# esp32.net
KiCad netlist of a schematic drawn in Altium Designer
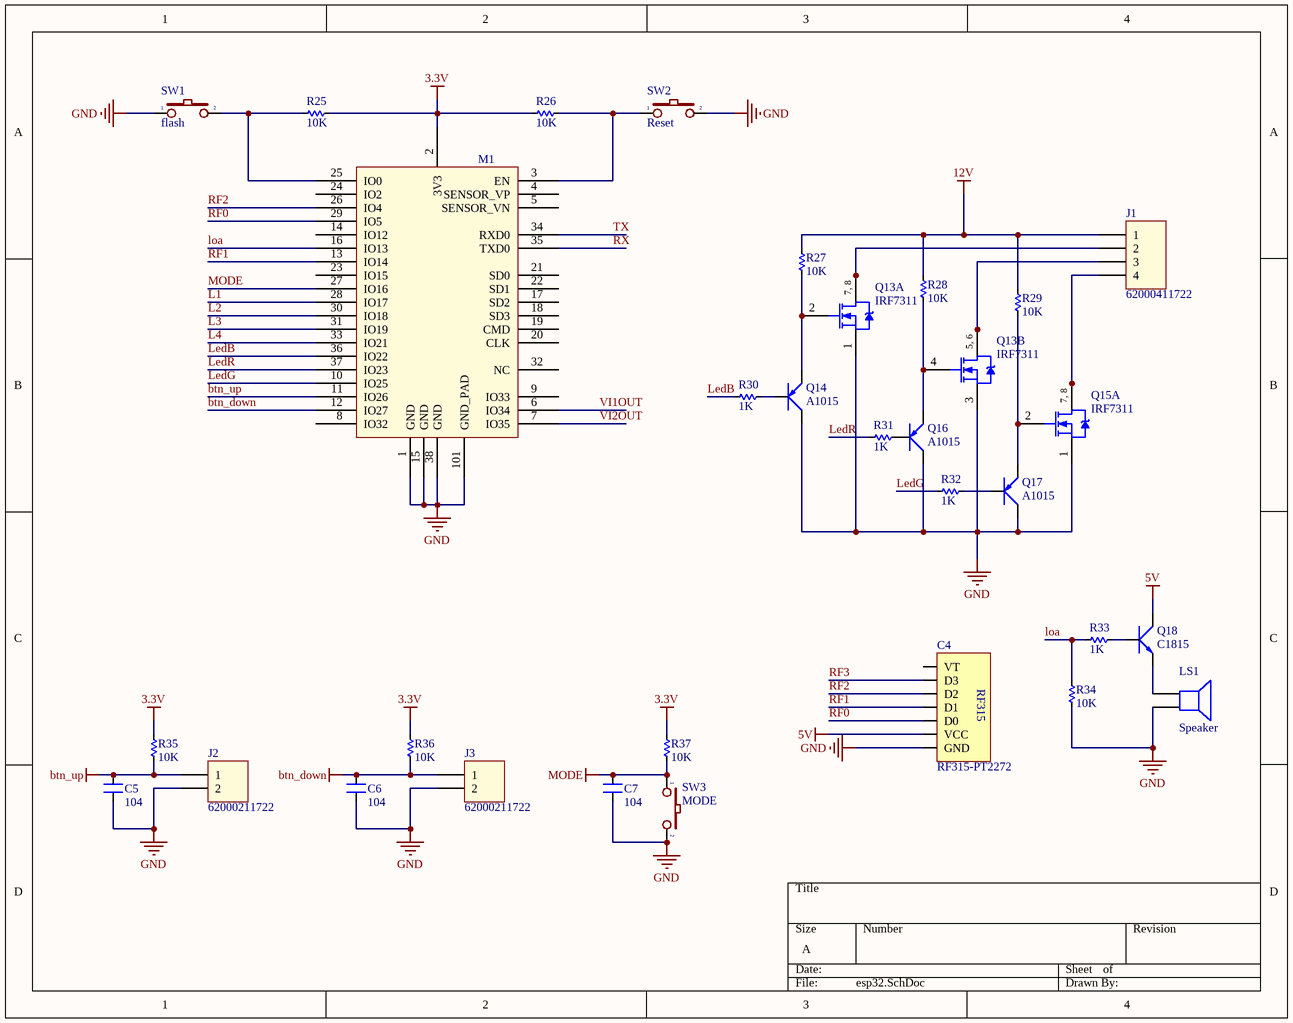
[diagram p0: esp32.SchDoc]

(export (version "E")
  (design (tool "Eeschema 10.0.6"))
  (components
    (comp (ref "C4")
      (value "RF315-PT2272")
      (footprint "RF315-2272")
      (fields
        (field (name "MANUFACTURER") "Würth Elektronik eiSos GmbH")
        (field (name "PARTNO") "613004143121")
        (field (name "CREATED BY") "Karrer Zheng")
      )
      (libsource (lib "LIBRARY") (part "RF315-PT2272"))
    )
    (comp (ref "C5")
      (value "104")
      (footprint "SM-CAP-0805")
      (fields (field (name "DESIGNED BY") "VanDungEvn"))
      (libsource (lib "electronicvn-library1") (part "CN"))
    )
    (comp (ref "C6")
      (value "104")
      (footprint "SM-CAP-0805")
      (fields (field (name "DESIGNED BY") "VanDungEvn"))
      (libsource (lib "electronicvn-library1") (part "CN"))
    )
    (comp (ref "C7")
      (value "104")
      (footprint "SM-CAP-0805")
      (fields (field (name "DESIGNED BY") "VanDungEvn"))
      (libsource (lib "electronicvn-library1") (part "CN"))
    )
    (comp (ref "J1")
      (value "62000411722")
      (footprint "62000411722")
      (description "WR-WTB 2.00mm Male Horizontal Shrouded Header, 4p")
      (fields (field (name "PUBLISHER") "Wurth Elektronik"))
      (libsource (lib "Header2.0") (part "62000411722"))
    )
    (comp (ref "J2")
      (value "62000211722")
      (footprint "62000211722")
      (description "WR-WTB 2.00mm Male Horizontal Shrouded Header, 2p")
      (fields (field (name "PUBLISHER") "Wurth Elektronik"))
      (libsource (lib "Header2.0") (part "62000211722"))
    )
    (comp (ref "J3")
      (value "62000211722")
      (footprint "62000211722")
      (description "WR-WTB 2.00mm Male Horizontal Shrouded Header, 2p")
      (fields (field (name "PUBLISHER") "Wurth Elektronik"))
      (libsource (lib "Header2.0") (part "62000211722"))
    )
    (comp (ref "LS1")
      (value "Speaker")
      (footprint "SPEAKER")
      (description "Loudspeaker")
      (fields (field (name "PUBLISHER") "Altium Limited"))
      (libsource (lib "LIBTanCN") (part "Speaker"))
    )
    (comp (ref "M1")
      (value "ESP32S_Module")
      (footprint "ESP32S")
      (description "Esp-32S")
      (libsource (lib "ESP32S") (part "ESP32S_Module"))
    )
    (comp (ref "Q13")
      (value "IRF7311")
      (footprint "SO-8_N")
      (description "HEXFET Power MOSFET")
      (fields (field (name "PUBLISHER") "Altium Limited"))
      (libsource (lib "IR Discrete MOSFET - Power") (part "IRF7101"))
    )
    (comp (ref "Q14")
      (value "A1015")
      (footprint "SOT23B")
      (description "PNP 600mW, ECB")
      (libsource (lib "electronicvn-library1") (part "A1015"))
    )
    (comp (ref "Q15")
      (value "IRF7311")
      (footprint "SO-8_N")
      (description "HEXFET Power MOSFET")
      (fields (field (name "PUBLISHER") "Altium Limited"))
      (libsource (lib "IR Discrete MOSFET - Power") (part "IRF7101"))
    )
    (comp (ref "Q16")
      (value "A1015")
      (footprint "SOT23B")
      (description "PNP 600mW, ECB")
      (libsource (lib "electronicvn-library1") (part "A1015"))
    )
    (comp (ref "Q17")
      (value "A1015")
      (footprint "SOT23B")
      (description "PNP 600mW, ECB")
      (libsource (lib "electronicvn-library1") (part "A1015"))
    )
    (comp (ref "Q18")
      (value "C1815")
      (footprint "SOT23B")
      (description "NPN 600mW, ECB")
      (libsource (lib "electronicvn-library1") (part "C1815"))
    )
    (comp (ref "R25")
      (value "10K")
      (footprint "RES-SMD-0805")
      (description "Resistor")
      (fields
        (field (name "MANUFACTURER") "Generic Components")
        (field (name "PUBLISHER") "Altium Hobart Technology Centre")
      )
      (libsource (lib "LIBRARY") (part "Res-SMD"))
    )
    (comp (ref "R26")
      (value "10K")
      (footprint "RES-SMD-0805")
      (description "Resistor")
      (fields
        (field (name "MANUFACTURER") "Generic Components")
        (field (name "PUBLISHER") "Altium Hobart Technology Centre")
      )
      (libsource (lib "LIBRARY") (part "Res-SMD"))
    )
    (comp (ref "R27")
      (value "10K")
      (footprint "RES-SMD-0805")
      (description "Resistor")
      (fields
        (field (name "MANUFACTURER") "Generic Components")
        (field (name "PUBLISHER") "Altium Hobart Technology Centre")
      )
      (libsource (lib "LIBRARY") (part "Res-SMD"))
    )
    (comp (ref "R28")
      (value "10K")
      (footprint "RES-SMD-0805")
      (description "Resistor")
      (fields
        (field (name "MANUFACTURER") "Generic Components")
        (field (name "PUBLISHER") "Altium Hobart Technology Centre")
      )
      (libsource (lib "LIBRARY") (part "Res-SMD"))
    )
    (comp (ref "R29")
      (value "10K")
      (footprint "RES-SMD-0805")
      (description "Resistor")
      (fields
        (field (name "MANUFACTURER") "Generic Components")
        (field (name "PUBLISHER") "Altium Hobart Technology Centre")
      )
      (libsource (lib "LIBRARY") (part "Res-SMD"))
    )
    (comp (ref "R30")
      (value "1K")
      (footprint "RES-SMD-0805")
      (description "Resistor")
      (fields
        (field (name "MANUFACTURER") "Generic Components")
        (field (name "PUBLISHER") "Altium Hobart Technology Centre")
      )
      (libsource (lib "LIBRARY") (part "Res-SMD"))
    )
    (comp (ref "R31")
      (value "1K")
      (footprint "RES-SMD-0805")
      (description "Resistor")
      (fields
        (field (name "MANUFACTURER") "Generic Components")
        (field (name "PUBLISHER") "Altium Hobart Technology Centre")
      )
      (libsource (lib "LIBRARY") (part "Res-SMD"))
    )
    (comp (ref "R32")
      (value "1K")
      (footprint "RES-SMD-0805")
      (description "Resistor")
      (fields
        (field (name "MANUFACTURER") "Generic Components")
        (field (name "PUBLISHER") "Altium Hobart Technology Centre")
      )
      (libsource (lib "LIBRARY") (part "Res-SMD"))
    )
    (comp (ref "R33")
      (value "1K")
      (footprint "RES-SMD-0805")
      (description "Resistor")
      (fields
        (field (name "MANUFACTURER") "Generic Components")
        (field (name "PUBLISHER") "Altium Hobart Technology Centre")
      )
      (libsource (lib "LIBRARY") (part "Res-SMD"))
    )
    (comp (ref "R34")
      (value "10K")
      (footprint "RES-SMD-0805")
      (description "Resistor")
      (fields
        (field (name "MANUFACTURER") "Generic Components")
        (field (name "PUBLISHER") "Altium Hobart Technology Centre")
      )
      (libsource (lib "LIBRARY") (part "Res-SMD"))
    )
    (comp (ref "R35")
      (value "10K")
      (footprint "RES-SMD-0805")
      (description "Resistor")
      (fields
        (field (name "MANUFACTURER") "Generic Components")
        (field (name "PUBLISHER") "Altium Hobart Technology Centre")
      )
      (libsource (lib "LIBRARY") (part "Res-SMD"))
    )
    (comp (ref "R36")
      (value "10K")
      (footprint "RES-SMD-0805")
      (description "Resistor")
      (fields
        (field (name "MANUFACTURER") "Generic Components")
        (field (name "PUBLISHER") "Altium Hobart Technology Centre")
      )
      (libsource (lib "LIBRARY") (part "Res-SMD"))
    )
    (comp (ref "R37")
      (value "10K")
      (footprint "RES-SMD-0805")
      (description "Resistor")
      (fields
        (field (name "MANUFACTURER") "Generic Components")
        (field (name "PUBLISHER") "Altium Hobart Technology Centre")
      )
      (libsource (lib "LIBRARY") (part "Res-SMD"))
    )
    (comp (ref "SW1")
      (value "flash")
      (footprint "SW-DIP1-1")
      (description "Switch button 2 pin")
      (libsource (lib "LIBRARY") (part "SW2"))
    )
    (comp (ref "SW2")
      (value "Reset")
      (footprint "SW1-SMD")
      (description "Switch button 2 pin")
      (libsource (lib "LIBRARY") (part "SW2"))
    )
    (comp (ref "SW3")
      (value "MODE")
      (footprint "SW-DIP1-1")
      (description "Switch button 2 pin")
      (libsource (lib "LIBRARY") (part "SW2"))
    )
  )
  (nets
    (net (code "1") (name "/L1") (class "Default")
      (node (ref "M1") (pin "28") (pinfunction "IO17_28") (pintype "passive"))
    )
    (net (code "2") (name "/L2") (class "Default")
      (node (ref "M1") (pin "30") (pinfunction "IO18_30") (pintype "passive"))
    )
    (net (code "3") (name "/L3") (class "Default")
      (node (ref "M1") (pin "31") (pinfunction "IO19_31") (pintype "passive"))
    )
    (net (code "4") (name "/L4") (class "Default")
      (node (ref "M1") (pin "33") (pinfunction "IO21_33") (pintype "passive"))
    )
    (net (code "5") (name "/LedB") (class "Default")
      (node (ref "M1") (pin "36") (pinfunction "IO22_36") (pintype "passive"))
      (node (ref "R30") (pin "2") (pinfunction "2_2") (pintype "passive"))
    )
    (net (code "6") (name "/LedG") (class "Default")
      (node (ref "M1") (pin "10") (pinfunction "IO25_10") (pintype "passive"))
      (node (ref "R32") (pin "2") (pinfunction "2_2") (pintype "passive"))
    )
    (net (code "7") (name "/LedR") (class "Default")
      (node (ref "M1") (pin "37") (pinfunction "IO23_37") (pintype "passive"))
      (node (ref "R31") (pin "2") (pinfunction "2_2") (pintype "passive"))
    )
    (net (code "8") (name "/RF0") (class "Default")
      (node (ref "C4") (pin "5") (pinfunction "D0_5") (pintype "passive"))
      (node (ref "M1") (pin "29") (pinfunction "IO5_29") (pintype "passive"))
    )
    (net (code "9") (name "/RF1") (class "Default")
      (node (ref "C4") (pin "4") (pinfunction "D1_4") (pintype "passive"))
      (node (ref "M1") (pin "13") (pinfunction "IO14_13") (pintype "passive"))
    )
    (net (code "10") (name "/RF2") (class "Default")
      (node (ref "C4") (pin "3") (pinfunction "D2_3") (pintype "passive"))
      (node (ref "M1") (pin "26") (pinfunction "IO4_26") (pintype "passive"))
    )
    (net (code "11") (name "/RF3") (class "Default")
      (node (ref "C4") (pin "2") (pinfunction "D3_2") (pintype "passive"))
    )
    (net (code "12") (name "/RX") (class "Default")
      (node (ref "M1") (pin "35") (pinfunction "TXD0_35") (pintype "passive"))
    )
    (net (code "13") (name "/TX") (class "Default")
      (node (ref "M1") (pin "34") (pinfunction "RXD0_34") (pintype "passive"))
    )
    (net (code "14") (name "/VI1OUT") (class "Default")
      (node (ref "M1") (pin "6") (pinfunction "IO34_6") (pintype "passive"))
    )
    (net (code "15") (name "/VI2OUT") (class "Default")
      (node (ref "M1") (pin "7") (pinfunction "IO35_7") (pintype "passive"))
    )
    (net (code "16") (name "/loa") (class "Default")
      (node (ref "M1") (pin "16") (pinfunction "IO13_16") (pintype "passive"))
      (node (ref "R33") (pin "2") (pinfunction "2_2") (pintype "passive"))
      (node (ref "R34") (pin "1") (pinfunction "1_1") (pintype "passive"))
    )
    (net (code "17") (name "3.3V") (class "Default")
      (node (ref "M1") (pin "2") (pinfunction "3V3_2") (pintype "power_in"))
      (node (ref "R25") (pin "2") (pinfunction "2_2") (pintype "passive"))
      (node (ref "R26") (pin "1") (pinfunction "1_1") (pintype "passive"))
      (node (ref "R35") (pin "2") (pinfunction "2_2") (pintype "passive"))
      (node (ref "R36") (pin "2") (pinfunction "2_2") (pintype "passive"))
      (node (ref "R37") (pin "2") (pinfunction "2_2") (pintype "passive"))
    )
    (net (code "18") (name "5V") (class "Default")
      (node (ref "C4") (pin "6") (pinfunction "VCC_6") (pintype "passive"))
      (node (ref "Q18") (pin "2") (pinfunction "C_2") (pintype "passive"))
    )
    (net (code "19") (name "12V") (class "Default")
      (node (ref "J1") (pin "1") (pinfunction "1_1") (pintype "passive"))
      (node (ref "R27") (pin "1") (pinfunction "1_1") (pintype "passive"))
      (node (ref "R28") (pin "1") (pinfunction "1_1") (pintype "passive"))
      (node (ref "R29") (pin "1") (pinfunction "1_1") (pintype "passive"))
    )
    (net (code "20") (name "GND") (class "Default")
      (node (ref "C4") (pin "7") (pinfunction "GND_7") (pintype "passive"))
      (node (ref "C5") (pin "1") (pinfunction "1_1") (pintype "passive"))
      (node (ref "C6") (pin "1") (pinfunction "1_1") (pintype "passive"))
      (node (ref "C7") (pin "1") (pinfunction "1_1") (pintype "passive"))
      (node (ref "J2") (pin "2") (pinfunction "2_2") (pintype "passive"))
      (node (ref "J3") (pin "2") (pinfunction "2_2") (pintype "passive"))
      (node (ref "LS1") (pin "2") (pinfunction "2_2") (pintype "passive"))
      (node (ref "M1") (pin "1") (pinfunction "GND_1") (pintype "power_in"))
      (node (ref "M1") (pin "101") (pinfunction "GND_PAD_101") (pintype "power_in"))
      (node (ref "M1") (pin "15") (pinfunction "GND_15") (pintype "power_in"))
      (node (ref "M1") (pin "38") (pinfunction "GND_38") (pintype "power_in"))
      (node (ref "Q13") (pin "1") (pinfunction "S_1") (pintype "passive"))
      (node (ref "Q13") (pin "3") (pinfunction "S_3") (pintype "passive"))
      (node (ref "Q14") (pin "2") (pinfunction "C_2") (pintype "passive"))
      (node (ref "Q15") (pin "1") (pinfunction "S_1") (pintype "passive"))
      (node (ref "Q16") (pin "2") (pinfunction "C_2") (pintype "passive"))
      (node (ref "Q17") (pin "2") (pinfunction "C_2") (pintype "passive"))
      (node (ref "R34") (pin "2") (pinfunction "2_2") (pintype "passive"))
      (node (ref "SW1") (pin "1") (pinfunction "1_1") (pintype "passive"))
      (node (ref "SW2") (pin "2") (pinfunction "2_2") (pintype "passive"))
      (node (ref "SW3") (pin "2") (pinfunction "2_2") (pintype "passive"))
    )
    (net (code "21") (name "MODE") (class "Default")
      (node (ref "C7") (pin "2") (pinfunction "2_2") (pintype "passive"))
      (node (ref "M1") (pin "27") (pinfunction "IO16_27") (pintype "passive"))
      (node (ref "R37") (pin "1") (pinfunction "1_1") (pintype "passive"))
      (node (ref "SW3") (pin "1") (pinfunction "1_1") (pintype "passive"))
    )
    (net (code "22") (name "Net-(J1-Pad2)") (class "Default")
      (node (ref "J1") (pin "2") (pinfunction "2_2") (pintype "passive"))
      (node (ref "Q13") (pin "7") (pinfunction "D_7") (pintype "passive"))
      (node (ref "Q13") (pin "8") (pinfunction "D_8") (pintype "passive"))
    )
    (net (code "23") (name "Net-(J1-Pad3)") (class "Default")
      (node (ref "J1") (pin "3") (pinfunction "3_3") (pintype "passive"))
      (node (ref "Q13") (pin "5") (pinfunction "D_5") (pintype "passive"))
      (node (ref "Q13") (pin "6") (pinfunction "D_6") (pintype "passive"))
    )
    (net (code "24") (name "Net-(J1-Pad4)") (class "Default")
      (node (ref "J1") (pin "4") (pinfunction "4_4") (pintype "passive"))
      (node (ref "Q15") (pin "7") (pinfunction "D_7") (pintype "passive"))
      (node (ref "Q15") (pin "8") (pinfunction "D_8") (pintype "passive"))
    )
    (net (code "25") (name "Net-(M1-EN)") (class "Default")
      (node (ref "M1") (pin "3") (pinfunction "EN_3") (pintype "power_in"))
      (node (ref "R26") (pin "2") (pinfunction "2_2") (pintype "passive"))
      (node (ref "SW2") (pin "1") (pinfunction "1_1") (pintype "passive"))
    )
    (net (code "26") (name "Net-(M1-IO0)") (class "Default")
      (node (ref "M1") (pin "25") (pinfunction "IO0_25") (pintype "passive"))
      (node (ref "R25") (pin "1") (pinfunction "1_1") (pintype "passive"))
      (node (ref "SW1") (pin "2") (pinfunction "2_2") (pintype "passive"))
    )
    (net (code "27") (name "Net-(Q13A-G)") (class "Default")
      (node (ref "Q13") (pin "2") (pinfunction "G_2") (pintype "passive"))
      (node (ref "Q14") (pin "1") (pinfunction "E_1") (pintype "passive"))
      (node (ref "R27") (pin "2") (pinfunction "2_2") (pintype "passive"))
    )
    (net (code "28") (name "Net-(Q13B-G)") (class "Default")
      (node (ref "Q13") (pin "4") (pinfunction "G_4") (pintype "passive"))
      (node (ref "Q16") (pin "1") (pinfunction "E_1") (pintype "passive"))
      (node (ref "R28") (pin "2") (pinfunction "2_2") (pintype "passive"))
    )
    (net (code "29") (name "Net-(Q14-B)") (class "Default")
      (node (ref "Q14") (pin "3") (pinfunction "B_3") (pintype "passive"))
      (node (ref "R30") (pin "1") (pinfunction "1_1") (pintype "passive"))
    )
    (net (code "30") (name "Net-(Q15A-G)") (class "Default")
      (node (ref "Q15") (pin "2") (pinfunction "G_2") (pintype "passive"))
      (node (ref "Q17") (pin "1") (pinfunction "E_1") (pintype "passive"))
      (node (ref "R29") (pin "2") (pinfunction "2_2") (pintype "passive"))
    )
    (net (code "31") (name "Net-(Q16-B)") (class "Default")
      (node (ref "Q16") (pin "3") (pinfunction "B_3") (pintype "passive"))
      (node (ref "R31") (pin "1") (pinfunction "1_1") (pintype "passive"))
    )
    (net (code "32") (name "Net-(Q17-B)") (class "Default")
      (node (ref "Q17") (pin "3") (pinfunction "B_3") (pintype "passive"))
      (node (ref "R32") (pin "1") (pinfunction "1_1") (pintype "passive"))
    )
    (net (code "33") (name "Net-(Q18-B)") (class "Default")
      (node (ref "Q18") (pin "3") (pinfunction "B_3") (pintype "passive"))
      (node (ref "R33") (pin "1") (pinfunction "1_1") (pintype "passive"))
    )
    (net (code "34") (name "Net-(Q18-E)") (class "Default")
      (node (ref "LS1") (pin "1") (pinfunction "1_1") (pintype "passive"))
      (node (ref "Q18") (pin "1") (pinfunction "E_1") (pintype "passive"))
    )
    (net (code "35") (name "btn_down") (class "Default")
      (node (ref "C6") (pin "2") (pinfunction "2_2") (pintype "passive"))
      (node (ref "J3") (pin "1") (pinfunction "1_1") (pintype "passive"))
      (node (ref "M1") (pin "12") (pinfunction "IO27_12") (pintype "passive"))
      (node (ref "R36") (pin "1") (pinfunction "1_1") (pintype "passive"))
    )
    (net (code "36") (name "btn_up") (class "Default")
      (node (ref "C5") (pin "2") (pinfunction "2_2") (pintype "passive"))
      (node (ref "J2") (pin "1") (pinfunction "1_1") (pintype "passive"))
      (node (ref "M1") (pin "11") (pinfunction "IO26_11") (pintype "passive"))
      (node (ref "R35") (pin "1") (pinfunction "1_1") (pintype "passive"))
    )
    (net (code "37") (name "unconnected-(C4-VT-Pad1)") (class "Default")
      (node (ref "C4") (pin "1") (pinfunction "VT_1") (pintype "passive"))
    )
    (net (code "38") (name "unconnected-(M1-CLK-Pad20)") (class "Default")
      (node (ref "M1") (pin "20") (pinfunction "CLK_20") (pintype "passive"))
    )
    (net (code "39") (name "unconnected-(M1-CMD-Pad19)") (class "Default")
      (node (ref "M1") (pin "19") (pinfunction "CMD_19") (pintype "passive"))
    )
    (net (code "40") (name "unconnected-(M1-IO2-Pad24)") (class "Default")
      (node (ref "M1") (pin "24") (pinfunction "IO2_24") (pintype "passive"))
    )
    (net (code "41") (name "unconnected-(M1-IO12-Pad14)") (class "Default")
      (node (ref "M1") (pin "14") (pinfunction "IO12_14") (pintype "passive"))
    )
    (net (code "42") (name "unconnected-(M1-IO15-Pad23)") (class "Default")
      (node (ref "M1") (pin "23") (pinfunction "IO15_23") (pintype "passive"))
    )
    (net (code "43") (name "unconnected-(M1-IO32-Pad8)") (class "Default")
      (node (ref "M1") (pin "8") (pinfunction "IO32_8") (pintype "passive"))
    )
    (net (code "44") (name "unconnected-(M1-IO33-Pad9)") (class "Default")
      (node (ref "M1") (pin "9") (pinfunction "IO33_9") (pintype "passive"))
    )
    (net (code "45") (name "unconnected-(M1-NC-Pad32)") (class "Default")
      (node (ref "M1") (pin "32") (pinfunction "NC_32") (pintype "passive"))
    )
    (net (code "46") (name "unconnected-(M1-SD0-Pad21)") (class "Default")
      (node (ref "M1") (pin "21") (pinfunction "SD0_21") (pintype "passive"))
    )
    (net (code "47") (name "unconnected-(M1-SD1-Pad22)") (class "Default")
      (node (ref "M1") (pin "22") (pinfunction "SD1_22") (pintype "passive"))
    )
    (net (code "48") (name "unconnected-(M1-SD2-Pad17)") (class "Default")
      (node (ref "M1") (pin "17") (pinfunction "SD2_17") (pintype "passive"))
    )
    (net (code "49") (name "unconnected-(M1-SD3-Pad18)") (class "Default")
      (node (ref "M1") (pin "18") (pinfunction "SD3_18") (pintype "passive"))
    )
    (net (code "50") (name "unconnected-(M1-SENSOR_VN-Pad5)") (class "Default")
      (node (ref "M1") (pin "5") (pinfunction "SENSOR_VN_5") (pintype "passive"))
    )
    (net (code "51") (name "unconnected-(M1-SENSOR_VP-Pad4)") (class "Default")
      (node (ref "M1") (pin "4") (pinfunction "SENSOR_VP_4") (pintype "passive"))
    )
  )
)
